# Pro_Trinket_Keyboard_V3_1.net
KiCad netlist of a schematic drawn in EAGLE
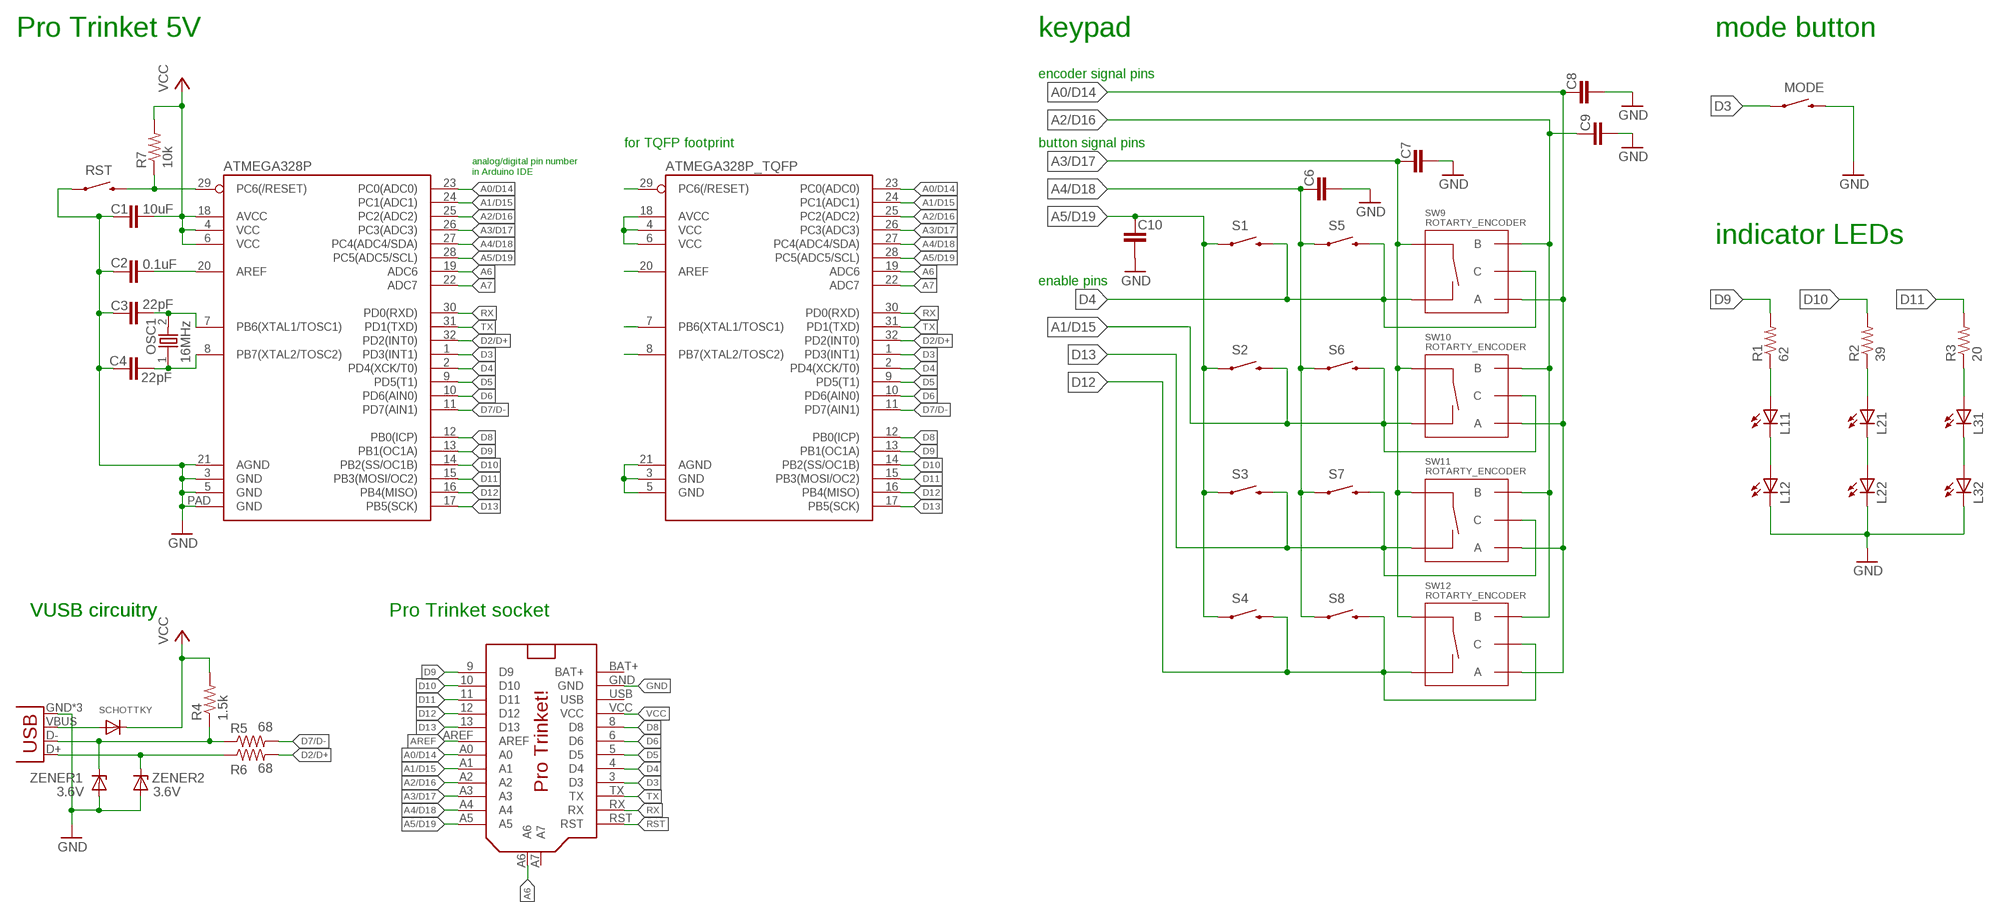
[diagram p0: schematic, sheet 1]

(export (version "E")
  (design (tool "Eeschema 10.0.6"))
  (components
    (comp (ref "ATMEGA328P")
      (value "ATMEGA328P_MLFMLF32")
      (footprint "eagle-import:MLF32-PAD")
      (libsource (lib "eagle-import") (part "ATMEGA328P_MLFMLF32"))
    )
    (comp (ref "ATMEGA328P_TQFP")
      (value "ATMEGA328P_TQFP")
      (footprint "eagle-import:TQFP32-08")
      (libsource (lib "eagle-import") (part "ATMEGA328P_TQFP"))
    )
    (comp (ref "C1")
      (value "10uF")
      (footprint "eagle-import:0603-CAP")
      (libsource (lib "eagle-import") (part "10UF-6.3V-20%(0603)"))
    )
    (comp (ref "C2")
      (value "0.1uF")
      (footprint "eagle-import:0603-CAP")
      (libsource (lib "eagle-import") (part "22PF-50V-5%(0603)"))
    )
    (comp (ref "C3")
      (value "22pF")
      (footprint "eagle-import:0603-CAP")
      (libsource (lib "eagle-import") (part "22PF-50V-5%(0603)"))
    )
    (comp (ref "C4")
      (value "22pF")
      (footprint "eagle-import:0603-CAP")
      (libsource (lib "eagle-import") (part "22PF-50V-5%(0603)"))
    )
    (comp (ref "C6")
      (value "22PF-50V-5%(0603)")
      (footprint "eagle-import:0603-CAP")
      (libsource (lib "eagle-import") (part "22PF-50V-5%(0603)"))
    )
    (comp (ref "C7")
      (value "22PF-50V-5%(0603)")
      (footprint "eagle-import:0603-CAP")
      (libsource (lib "eagle-import") (part "22PF-50V-5%(0603)"))
    )
    (comp (ref "C8")
      (value "22PF-50V-5%(0603)")
      (footprint "eagle-import:0603-CAP")
      (libsource (lib "eagle-import") (part "22PF-50V-5%(0603)"))
    )
    (comp (ref "C9")
      (value "22PF-50V-5%(0603)")
      (footprint "eagle-import:0603-CAP")
      (libsource (lib "eagle-import") (part "22PF-50V-5%(0603)"))
    )
    (comp (ref "C10")
      (value "22PF-50V-5%(0603)")
      (footprint "eagle-import:0603-CAP")
      (libsource (lib "eagle-import") (part "22PF-50V-5%(0603)"))
    )
    (comp (ref "JP1")
      (value "USB-MICROB")
      (footprint "eagle-import:USB-MICROB")
      (libsource (lib "eagle-import") (part "USB-MICROB"))
    )
    (comp (ref "L11")
      (value "LEDCHIPLED_0805")
      (footprint "eagle-import:CHIPLED_0805")
      (libsource (lib "eagle-import") (part "LEDCHIPLED_0805"))
    )
    (comp (ref "L12")
      (value "LEDCHIPLED_0805")
      (footprint "eagle-import:CHIPLED_0805")
      (libsource (lib "eagle-import") (part "LEDCHIPLED_0805"))
    )
    (comp (ref "L21")
      (value "LEDCHIPLED_0805")
      (footprint "eagle-import:CHIPLED_0805")
      (libsource (lib "eagle-import") (part "LEDCHIPLED_0805"))
    )
    (comp (ref "L22")
      (value "LEDCHIPLED_0805")
      (footprint "eagle-import:CHIPLED_0805")
      (libsource (lib "eagle-import") (part "LEDCHIPLED_0805"))
    )
    (comp (ref "L31")
      (value "LEDCHIPLED_0805")
      (footprint "eagle-import:CHIPLED_0805")
      (libsource (lib "eagle-import") (part "LEDCHIPLED_0805"))
    )
    (comp (ref "L32")
      (value "LEDCHIPLED_0805")
      (footprint "eagle-import:CHIPLED_0805")
      (libsource (lib "eagle-import") (part "LEDCHIPLED_0805"))
    )
    (comp (ref "MODE")
      (value "SWITCH-MOMENTARY-2SIDE_EZ")
      (footprint "eagle-import:TACTILE-PTH-SIDEEZ")
      (libsource (lib "eagle-import") (part "SWITCH-MOMENTARY-2SIDE_EZ"))
    )
    (comp (ref "OSC1")
      (value "16MHz")
      (footprint "eagle-import:HC-49U")
      (libsource (lib "eagle-import") (part "OSC-XTAL-HC-49U-SMD"))
    )
    (comp (ref "R1")
      (value "62")
      (footprint "eagle-import:M0805")
      (libsource (lib "eagle-import") (part "R-US_M0805"))
    )
    (comp (ref "R2")
      (value "39")
      (footprint "eagle-import:M0805")
      (libsource (lib "eagle-import") (part "R-US_M0805"))
    )
    (comp (ref "R3")
      (value "20")
      (footprint "eagle-import:M0805")
      (libsource (lib "eagle-import") (part "R-US_M0805"))
    )
    (comp (ref "R4")
      (value "1.5k")
      (footprint "eagle-import:0805")
      (libsource (lib "eagle-import") (part "RESISTOR0805-RES"))
    )
    (comp (ref "R5")
      (value "68")
      (footprint "eagle-import:0805")
      (libsource (lib "eagle-import") (part "RESISTOR0805-RES"))
    )
    (comp (ref "R6")
      (value "68")
      (footprint "eagle-import:0805")
      (libsource (lib "eagle-import") (part "RESISTOR0805-RES"))
    )
    (comp (ref "R7")
      (value "10k")
      (footprint "eagle-import:0805")
      (libsource (lib "eagle-import") (part "RESISTOR0805-RES"))
    )
    (comp (ref "RST")
      (value "SWITCH-MOMENTARY-2SIDE_EZ")
      (footprint "eagle-import:TACTILE-PTH-SIDEEZ")
      (libsource (lib "eagle-import") (part "SWITCH-MOMENTARY-2SIDE_EZ"))
    )
    (comp (ref "S1")
      (value "SWITCH-MOMENTARY-212MM")
      (footprint "eagle-import:TACTILE-PTH-12MM")
      (libsource (lib "eagle-import") (part "SWITCH-MOMENTARY-212MM"))
    )
    (comp (ref "S2")
      (value "SWITCH-MOMENTARY-212MM")
      (footprint "eagle-import:TACTILE-PTH-12MM")
      (libsource (lib "eagle-import") (part "SWITCH-MOMENTARY-212MM"))
    )
    (comp (ref "S3")
      (value "SWITCH-MOMENTARY-212MM")
      (footprint "eagle-import:TACTILE-PTH-12MM")
      (libsource (lib "eagle-import") (part "SWITCH-MOMENTARY-212MM"))
    )
    (comp (ref "S4")
      (value "SWITCH-MOMENTARY-212MM")
      (footprint "eagle-import:TACTILE-PTH-12MM")
      (libsource (lib "eagle-import") (part "SWITCH-MOMENTARY-212MM"))
    )
    (comp (ref "S5")
      (value "SWITCH-MOMENTARY-212MM")
      (footprint "eagle-import:TACTILE-PTH-12MM")
      (libsource (lib "eagle-import") (part "SWITCH-MOMENTARY-212MM"))
    )
    (comp (ref "S6")
      (value "SWITCH-MOMENTARY-212MM")
      (footprint "eagle-import:TACTILE-PTH-12MM")
      (libsource (lib "eagle-import") (part "SWITCH-MOMENTARY-212MM"))
    )
    (comp (ref "S7")
      (value "SWITCH-MOMENTARY-212MM")
      (footprint "eagle-import:TACTILE-PTH-12MM")
      (libsource (lib "eagle-import") (part "SWITCH-MOMENTARY-212MM"))
    )
    (comp (ref "S8")
      (value "SWITCH-MOMENTARY-212MM")
      (footprint "eagle-import:TACTILE-PTH-12MM")
      (libsource (lib "eagle-import") (part "SWITCH-MOMENTARY-212MM"))
    )
    (comp (ref "SCHOTTKY")
      (value "DIODESMA")
      (footprint "eagle-import:SMADIODE")
      (libsource (lib "eagle-import") (part "DIODESMA"))
    )
    (comp (ref "SW9")
      (value "ROTARTY_ENCODER")
      (footprint "eagle-import:ROTARY_ENC_PLAIN")
      (libsource (lib "eagle-import") (part "ROTARTY_ENCODER"))
    )
    (comp (ref "SW10")
      (value "ROTARTY_ENCODER")
      (footprint "eagle-import:ROTARY_ENC_PLAIN")
      (libsource (lib "eagle-import") (part "ROTARTY_ENCODER"))
    )
    (comp (ref "SW11")
      (value "ROTARTY_ENCODER")
      (footprint "eagle-import:ROTARY_ENC_PLAIN")
      (libsource (lib "eagle-import") (part "ROTARTY_ENCODER"))
    )
    (comp (ref "SW12")
      (value "ROTARTY_ENCODER")
      (footprint "eagle-import:ROTARY_ENC_PLAIN")
      (libsource (lib "eagle-import") (part "ROTARTY_ENCODER"))
    )
    (comp (ref "U$2")
      (value "PRO_TRINKET")
      (footprint "eagle-import:PROTRINKET")
      (libsource (lib "eagle-import") (part "PRO_TRINKET"))
    )
    (comp (ref "ZENER1")
      (value "3.6V")
      (footprint "eagle-import:SOD80C")
      (libsource (lib "eagle-import") (part "ZENER-DIODESOD80C"))
    )
    (comp (ref "ZENER2")
      (value "3.6V")
      (footprint "eagle-import:SOD80C")
      (libsource (lib "eagle-import") (part "ZENER-DIODESOD80C"))
    )
  )
  (nets
    (net (code "1") (name "/BAT+") (class "Default")
      (node (ref "U$2") (pin "BAT+") (pinfunction "BAT+_BAT+") (pintype "power_in"))
    )
    (net (code "2") (name "/USB") (class "Default")
      (node (ref "U$2") (pin "USB") (pinfunction "USB_USB") (pintype "power_in"))
    )
    (net (code "3") (name "/XTAL1") (class "Default")
      (node (ref "ATMEGA328P") (pin "7") (pinfunction "PB6(XTAL1/TOSC1)_7") (pintype "bidirectional"))
      (node (ref "ATMEGA328P_TQFP") (pin "7") (pinfunction "PB6(XTAL1/TOSC1)_7") (pintype "bidirectional"))
      (node (ref "C3") (pin "2") (pinfunction "2_2") (pintype "passive"))
      (node (ref "OSC1") (pin "2") (pinfunction "2_2") (pintype "passive"))
    )
    (net (code "4") (name "/XTAL2") (class "Default")
      (node (ref "ATMEGA328P") (pin "8") (pinfunction "PB7(XTAL2/TOSC2)_8") (pintype "bidirectional"))
      (node (ref "ATMEGA328P_TQFP") (pin "8") (pinfunction "PB7(XTAL2/TOSC2)_8") (pintype "bidirectional"))
      (node (ref "C4") (pin "1") (pinfunction "1_1") (pintype "passive"))
      (node (ref "OSC1") (pin "1") (pinfunction "1_1") (pintype "passive"))
    )
    (net (code "5") (name "A0{slash}D14") (class "Default")
      (node (ref "ATMEGA328P") (pin "23") (pinfunction "PC0(ADC0)_23") (pintype "bidirectional"))
      (node (ref "ATMEGA328P_TQFP") (pin "23") (pinfunction "PC0(ADC0)_23") (pintype "bidirectional"))
      (node (ref "C8") (pin "1") (pinfunction "1_1") (pintype "passive"))
      (node (ref "SW10") (pin "A") (pinfunction "A_A") (pintype "bidirectional"))
      (node (ref "SW11") (pin "A") (pinfunction "A_A") (pintype "bidirectional"))
      (node (ref "SW12") (pin "A") (pinfunction "A_A") (pintype "bidirectional"))
      (node (ref "SW9") (pin "A") (pinfunction "A_A") (pintype "bidirectional"))
      (node (ref "U$2") (pin "A0") (pinfunction "A0_A0") (pintype "bidirectional"))
    )
    (net (code "6") (name "A1{slash}D15") (class "Default")
      (node (ref "ATMEGA328P") (pin "24") (pinfunction "PC1(ADC1)_24") (pintype "bidirectional"))
      (node (ref "ATMEGA328P_TQFP") (pin "24") (pinfunction "PC1(ADC1)_24") (pintype "bidirectional"))
      (node (ref "S2") (pin "3") (pinfunction "2_3") (pintype "passive"))
      (node (ref "S2") (pin "4") (pinfunction "2_4") (pintype "passive"))
      (node (ref "S6") (pin "3") (pinfunction "2_3") (pintype "passive"))
      (node (ref "S6") (pin "4") (pinfunction "2_4") (pintype "passive"))
      (node (ref "SW10") (pin "C") (pinfunction "C_C") (pintype "bidirectional"))
      (node (ref "SW10") (pin "SW-") (pinfunction "SW-_SW-") (pintype "bidirectional"))
      (node (ref "U$2") (pin "A1") (pinfunction "A1_A1") (pintype "bidirectional"))
    )
    (net (code "7") (name "A2{slash}D16") (class "Default")
      (node (ref "ATMEGA328P") (pin "25") (pinfunction "PC2(ADC2)_25") (pintype "bidirectional"))
      (node (ref "ATMEGA328P_TQFP") (pin "25") (pinfunction "PC2(ADC2)_25") (pintype "bidirectional"))
      (node (ref "C9") (pin "1") (pinfunction "1_1") (pintype "passive"))
      (node (ref "SW10") (pin "B") (pinfunction "B_B") (pintype "bidirectional"))
      (node (ref "SW11") (pin "B") (pinfunction "B_B") (pintype "bidirectional"))
      (node (ref "SW12") (pin "B") (pinfunction "B_B") (pintype "bidirectional"))
      (node (ref "SW9") (pin "B") (pinfunction "B_B") (pintype "bidirectional"))
      (node (ref "U$2") (pin "A2") (pinfunction "A2_A2") (pintype "bidirectional"))
    )
    (net (code "8") (name "A3{slash}D17") (class "Default")
      (node (ref "ATMEGA328P") (pin "26") (pinfunction "PC3(ADC3)_26") (pintype "bidirectional"))
      (node (ref "ATMEGA328P_TQFP") (pin "26") (pinfunction "PC3(ADC3)_26") (pintype "bidirectional"))
      (node (ref "C7") (pin "1") (pinfunction "1_1") (pintype "passive"))
      (node (ref "SW10") (pin "SW+") (pinfunction "SW+_SW+") (pintype "bidirectional"))
      (node (ref "SW11") (pin "SW+") (pinfunction "SW+_SW+") (pintype "bidirectional"))
      (node (ref "SW12") (pin "SW+") (pinfunction "SW+_SW+") (pintype "bidirectional"))
      (node (ref "SW9") (pin "SW+") (pinfunction "SW+_SW+") (pintype "bidirectional"))
      (node (ref "U$2") (pin "A3") (pinfunction "A3_A3") (pintype "bidirectional"))
    )
    (net (code "9") (name "A4{slash}D18") (class "Default")
      (node (ref "ATMEGA328P") (pin "27") (pinfunction "PC4(ADC4/SDA)_27") (pintype "bidirectional"))
      (node (ref "ATMEGA328P_TQFP") (pin "27") (pinfunction "PC4(ADC4/SDA)_27") (pintype "bidirectional"))
      (node (ref "C6") (pin "1") (pinfunction "1_1") (pintype "passive"))
      (node (ref "S5") (pin "1") (pinfunction "1_1") (pintype "passive"))
      (node (ref "S5") (pin "2") (pinfunction "1_2") (pintype "passive"))
      (node (ref "S6") (pin "1") (pinfunction "1_1") (pintype "passive"))
      (node (ref "S6") (pin "2") (pinfunction "1_2") (pintype "passive"))
      (node (ref "S7") (pin "1") (pinfunction "1_1") (pintype "passive"))
      (node (ref "S7") (pin "2") (pinfunction "1_2") (pintype "passive"))
      (node (ref "S8") (pin "1") (pinfunction "1_1") (pintype "passive"))
      (node (ref "S8") (pin "2") (pinfunction "1_2") (pintype "passive"))
      (node (ref "U$2") (pin "A4") (pinfunction "A4_A4") (pintype "bidirectional"))
    )
    (net (code "10") (name "A5{slash}D19") (class "Default")
      (node (ref "ATMEGA328P") (pin "28") (pinfunction "PC5(ADC5/SCL)_28") (pintype "bidirectional"))
      (node (ref "ATMEGA328P_TQFP") (pin "28") (pinfunction "PC5(ADC5/SCL)_28") (pintype "bidirectional"))
      (node (ref "C10") (pin "1") (pinfunction "1_1") (pintype "passive"))
      (node (ref "S1") (pin "1") (pinfunction "1_1") (pintype "passive"))
      (node (ref "S1") (pin "2") (pinfunction "1_2") (pintype "passive"))
      (node (ref "S2") (pin "1") (pinfunction "1_1") (pintype "passive"))
      (node (ref "S2") (pin "2") (pinfunction "1_2") (pintype "passive"))
      (node (ref "S3") (pin "1") (pinfunction "1_1") (pintype "passive"))
      (node (ref "S3") (pin "2") (pinfunction "1_2") (pintype "passive"))
      (node (ref "S4") (pin "1") (pinfunction "1_1") (pintype "passive"))
      (node (ref "S4") (pin "2") (pinfunction "1_2") (pintype "passive"))
      (node (ref "U$2") (pin "A5") (pinfunction "A5_A5") (pintype "bidirectional"))
    )
    (net (code "11") (name "A6") (class "Default")
      (node (ref "ATMEGA328P") (pin "19") (pinfunction "ADC6_19") (pintype "bidirectional"))
      (node (ref "ATMEGA328P_TQFP") (pin "19") (pinfunction "ADC6_19") (pintype "bidirectional"))
      (node (ref "U$2") (pin "A6") (pinfunction "A6_A6") (pintype "passive"))
    )
    (net (code "12") (name "A7") (class "Default")
      (node (ref "ATMEGA328P") (pin "22") (pinfunction "ADC7_22") (pintype "bidirectional"))
      (node (ref "ATMEGA328P_TQFP") (pin "22") (pinfunction "ADC7_22") (pintype "bidirectional"))
    )
    (net (code "13") (name "AREF") (class "Default")
      (node (ref "ATMEGA328P") (pin "20") (pinfunction "AREF_20") (pintype "bidirectional"))
      (node (ref "ATMEGA328P_TQFP") (pin "20") (pinfunction "AREF_20") (pintype "bidirectional"))
      (node (ref "C2") (pin "2") (pinfunction "2_2") (pintype "passive"))
      (node (ref "U$2") (pin "AREF") (pinfunction "AREF_AREF") (pintype "passive"))
    )
    (net (code "14") (name "D2{slash}D+") (class "Default")
      (node (ref "ATMEGA328P") (pin "32") (pinfunction "PD2(INT0)_32") (pintype "bidirectional"))
      (node (ref "ATMEGA328P_TQFP") (pin "32") (pinfunction "PD2(INT0)_32") (pintype "bidirectional"))
      (node (ref "R6") (pin "2") (pinfunction "2_2") (pintype "passive"))
    )
    (net (code "15") (name "D3") (class "Default")
      (node (ref "ATMEGA328P") (pin "1") (pinfunction "PD3(INT1)_1") (pintype "bidirectional"))
      (node (ref "ATMEGA328P_TQFP") (pin "1") (pinfunction "PD3(INT1)_1") (pintype "bidirectional"))
      (node (ref "MODE") (pin "1") (pinfunction "1_1") (pintype "passive"))
      (node (ref "U$2") (pin "3") (pinfunction "D3_3") (pintype "bidirectional"))
    )
    (net (code "16") (name "D4") (class "Default")
      (node (ref "ATMEGA328P") (pin "2") (pinfunction "PD4(XCK/T0)_2") (pintype "bidirectional"))
      (node (ref "ATMEGA328P_TQFP") (pin "2") (pinfunction "PD4(XCK/T0)_2") (pintype "bidirectional"))
      (node (ref "S1") (pin "3") (pinfunction "2_3") (pintype "passive"))
      (node (ref "S1") (pin "4") (pinfunction "2_4") (pintype "passive"))
      (node (ref "S5") (pin "3") (pinfunction "2_3") (pintype "passive"))
      (node (ref "S5") (pin "4") (pinfunction "2_4") (pintype "passive"))
      (node (ref "SW9") (pin "C") (pinfunction "C_C") (pintype "bidirectional"))
      (node (ref "SW9") (pin "SW-") (pinfunction "SW-_SW-") (pintype "bidirectional"))
      (node (ref "U$2") (pin "4") (pinfunction "D4_4") (pintype "bidirectional"))
    )
    (net (code "17") (name "D5") (class "Default")
      (node (ref "ATMEGA328P") (pin "9") (pinfunction "PD5(T1)_9") (pintype "bidirectional"))
      (node (ref "ATMEGA328P_TQFP") (pin "9") (pinfunction "PD5(T1)_9") (pintype "bidirectional"))
      (node (ref "U$2") (pin "5") (pinfunction "D5_5") (pintype "bidirectional"))
    )
    (net (code "18") (name "D6") (class "Default")
      (node (ref "ATMEGA328P") (pin "10") (pinfunction "PD6(AIN0)_10") (pintype "bidirectional"))
      (node (ref "ATMEGA328P_TQFP") (pin "10") (pinfunction "PD6(AIN0)_10") (pintype "bidirectional"))
      (node (ref "U$2") (pin "6") (pinfunction "D6_6") (pintype "bidirectional"))
    )
    (net (code "19") (name "D7{slash}D-") (class "Default")
      (node (ref "ATMEGA328P") (pin "11") (pinfunction "PD7(AIN1)_11") (pintype "bidirectional"))
      (node (ref "ATMEGA328P_TQFP") (pin "11") (pinfunction "PD7(AIN1)_11") (pintype "bidirectional"))
      (node (ref "R5") (pin "2") (pinfunction "2_2") (pintype "passive"))
    )
    (net (code "20") (name "D8") (class "Default")
      (node (ref "ATMEGA328P") (pin "12") (pinfunction "PB0(ICP)_12") (pintype "bidirectional"))
      (node (ref "ATMEGA328P_TQFP") (pin "12") (pinfunction "PB0(ICP)_12") (pintype "bidirectional"))
      (node (ref "U$2") (pin "8") (pinfunction "D8_8") (pintype "bidirectional"))
    )
    (net (code "21") (name "D9") (class "Default")
      (node (ref "ATMEGA328P") (pin "13") (pinfunction "PB1(OC1A)_13") (pintype "bidirectional"))
      (node (ref "ATMEGA328P_TQFP") (pin "13") (pinfunction "PB1(OC1A)_13") (pintype "bidirectional"))
      (node (ref "R1") (pin "2") (pinfunction "2_2") (pintype "passive"))
      (node (ref "U$2") (pin "9") (pinfunction "D9_9") (pintype "bidirectional"))
    )
    (net (code "22") (name "D10") (class "Default")
      (node (ref "ATMEGA328P") (pin "14") (pinfunction "PB2(SS/OC1B)_14") (pintype "bidirectional"))
      (node (ref "ATMEGA328P_TQFP") (pin "14") (pinfunction "PB2(SS/OC1B)_14") (pintype "bidirectional"))
      (node (ref "R2") (pin "2") (pinfunction "2_2") (pintype "passive"))
      (node (ref "U$2") (pin "10") (pinfunction "D10_10") (pintype "bidirectional"))
    )
    (net (code "23") (name "D11") (class "Default")
      (node (ref "ATMEGA328P") (pin "15") (pinfunction "PB3(MOSI/OC2)_15") (pintype "bidirectional"))
      (node (ref "ATMEGA328P_TQFP") (pin "15") (pinfunction "PB3(MOSI/OC2)_15") (pintype "bidirectional"))
      (node (ref "R3") (pin "2") (pinfunction "2_2") (pintype "passive"))
      (node (ref "U$2") (pin "11") (pinfunction "D11_11") (pintype "bidirectional"))
    )
    (net (code "24") (name "D12") (class "Default")
      (node (ref "ATMEGA328P") (pin "16") (pinfunction "PB4(MISO)_16") (pintype "bidirectional"))
      (node (ref "ATMEGA328P_TQFP") (pin "16") (pinfunction "PB4(MISO)_16") (pintype "bidirectional"))
      (node (ref "S4") (pin "3") (pinfunction "2_3") (pintype "passive"))
      (node (ref "S4") (pin "4") (pinfunction "2_4") (pintype "passive"))
      (node (ref "S8") (pin "3") (pinfunction "2_3") (pintype "passive"))
      (node (ref "S8") (pin "4") (pinfunction "2_4") (pintype "passive"))
      (node (ref "SW12") (pin "C") (pinfunction "C_C") (pintype "bidirectional"))
      (node (ref "SW12") (pin "SW-") (pinfunction "SW-_SW-") (pintype "bidirectional"))
      (node (ref "U$2") (pin "12") (pinfunction "D12_12") (pintype "bidirectional"))
    )
    (net (code "25") (name "D13") (class "Default")
      (node (ref "ATMEGA328P") (pin "17") (pinfunction "PB5(SCK)_17") (pintype "bidirectional"))
      (node (ref "ATMEGA328P_TQFP") (pin "17") (pinfunction "PB5(SCK)_17") (pintype "bidirectional"))
      (node (ref "S3") (pin "3") (pinfunction "2_3") (pintype "passive"))
      (node (ref "S3") (pin "4") (pinfunction "2_4") (pintype "passive"))
      (node (ref "S7") (pin "3") (pinfunction "2_3") (pintype "passive"))
      (node (ref "S7") (pin "4") (pinfunction "2_4") (pintype "passive"))
      (node (ref "SW11") (pin "C") (pinfunction "C_C") (pintype "bidirectional"))
      (node (ref "SW11") (pin "SW-") (pinfunction "SW-_SW-") (pintype "bidirectional"))
      (node (ref "U$2") (pin "13") (pinfunction "D13_13") (pintype "bidirectional"))
    )
    (net (code "26") (name "GND") (class "Default")
      (node (ref "ATMEGA328P") (pin "21") (pinfunction "AGND_21") (pintype "bidirectional"))
      (node (ref "ATMEGA328P") (pin "3") (pinfunction "GND_3") (pintype "bidirectional"))
      (node (ref "ATMEGA328P") (pin "5") (pinfunction "GND_5") (pintype "bidirectional"))
      (node (ref "ATMEGA328P") (pin "PAD") (pinfunction "GND_PAD") (pintype "bidirectional"))
      (node (ref "ATMEGA328P_TQFP") (pin "21") (pinfunction "AGND_21") (pintype "bidirectional"))
      (node (ref "ATMEGA328P_TQFP") (pin "3") (pinfunction "GND_3") (pintype "bidirectional"))
      (node (ref "ATMEGA328P_TQFP") (pin "5") (pinfunction "GND_5") (pintype "bidirectional"))
      (node (ref "C1") (pin "1") (pinfunction "1_1") (pintype "passive"))
      (node (ref "C10") (pin "2") (pinfunction "2_2") (pintype "passive"))
      (node (ref "C2") (pin "1") (pinfunction "1_1") (pintype "passive"))
      (node (ref "C3") (pin "1") (pinfunction "1_1") (pintype "passive"))
      (node (ref "C4") (pin "2") (pinfunction "2_2") (pintype "passive"))
      (node (ref "C6") (pin "2") (pinfunction "2_2") (pintype "passive"))
      (node (ref "C7") (pin "2") (pinfunction "2_2") (pintype "passive"))
      (node (ref "C8") (pin "2") (pinfunction "2_2") (pintype "passive"))
      (node (ref "C9") (pin "2") (pinfunction "2_2") (pintype "passive"))
      (node (ref "JP1") (pin "GND") (pinfunction "GND_GND") (pintype "bidirectional"))
      (node (ref "JP1") (pin "MT1") (pinfunction "GND_MT1") (pintype "bidirectional"))
      (node (ref "JP1") (pin "MT2") (pinfunction "GND_MT2") (pintype "bidirectional"))
      (node (ref "L12") (pin "C") (pinfunction "C_C") (pintype "passive"))
      (node (ref "L22") (pin "C") (pinfunction "C_C") (pintype "passive"))
      (node (ref "L32") (pin "C") (pinfunction "C_C") (pintype "passive"))
      (node (ref "MODE") (pin "2") (pinfunction "2_2") (pintype "passive"))
      (node (ref "RST") (pin "1") (pinfunction "1_1") (pintype "passive"))
      (node (ref "U$2") (pin "GND") (pinfunction "GND_GND") (pintype "power_in"))
      (node (ref "ZENER1") (pin "A") (pinfunction "A_A") (pintype "passive"))
      (node (ref "ZENER2") (pin "A") (pinfunction "A_A") (pintype "passive"))
    )
    (net (code "27") (name "Net-(JP1-PadD+)") (class "Default")
      (node (ref "JP1") (pin "D+") (pinfunction "D+_D+") (pintype "bidirectional"))
      (node (ref "R6") (pin "1") (pinfunction "1_1") (pintype "passive"))
      (node (ref "ZENER2") (pin "C") (pinfunction "C_C") (pintype "passive"))
    )
    (net (code "28") (name "Net-(JP1-PadD-)") (class "Default")
      (node (ref "JP1") (pin "D-") (pinfunction "D-_D-") (pintype "bidirectional"))
      (node (ref "R4") (pin "1") (pinfunction "1_1") (pintype "passive"))
      (node (ref "R5") (pin "1") (pinfunction "1_1") (pintype "passive"))
      (node (ref "ZENER1") (pin "C") (pinfunction "C_C") (pintype "passive"))
    )
    (net (code "29") (name "Net-(JP1-PadVBUS)") (class "Default")
      (node (ref "JP1") (pin "VBUS") (pinfunction "VBUS_VBUS") (pintype "bidirectional"))
      (node (ref "SCHOTTKY") (pin "A") (pinfunction "A_A") (pintype "passive"))
    )
    (net (code "30") (name "Net-(L11-PadA)") (class "Default")
      (node (ref "L11") (pin "A") (pinfunction "A_A") (pintype "passive"))
      (node (ref "R1") (pin "1") (pinfunction "1_1") (pintype "passive"))
    )
    (net (code "31") (name "Net-(L11-PadC)") (class "Default")
      (node (ref "L11") (pin "C") (pinfunction "C_C") (pintype "passive"))
      (node (ref "L12") (pin "A") (pinfunction "A_A") (pintype "passive"))
    )
    (net (code "32") (name "Net-(L21-PadA)") (class "Default")
      (node (ref "L21") (pin "A") (pinfunction "A_A") (pintype "passive"))
      (node (ref "R2") (pin "1") (pinfunction "1_1") (pintype "passive"))
    )
    (net (code "33") (name "Net-(L21-PadC)") (class "Default")
      (node (ref "L21") (pin "C") (pinfunction "C_C") (pintype "passive"))
      (node (ref "L22") (pin "A") (pinfunction "A_A") (pintype "passive"))
    )
    (net (code "34") (name "Net-(L31-PadA)") (class "Default")
      (node (ref "L31") (pin "A") (pinfunction "A_A") (pintype "passive"))
      (node (ref "R3") (pin "1") (pinfunction "1_1") (pintype "passive"))
    )
    (net (code "35") (name "Net-(L31-PadC)") (class "Default")
      (node (ref "L31") (pin "C") (pinfunction "C_C") (pintype "passive"))
      (node (ref "L32") (pin "A") (pinfunction "A_A") (pintype "passive"))
    )
    (net (code "36") (name "RST") (class "Default")
      (node (ref "ATMEGA328P") (pin "29") (pinfunction "PC6(/RESET)_29") (pintype "bidirectional"))
      (node (ref "ATMEGA328P_TQFP") (pin "29") (pinfunction "PC6(/RESET)_29") (pintype "bidirectional"))
      (node (ref "R7") (pin "1") (pinfunction "1_1") (pintype "passive"))
      (node (ref "RST") (pin "2") (pinfunction "2_2") (pintype "passive"))
      (node (ref "U$2") (pin "RST") (pinfunction "RST_RST") (pintype "passive"))
    )
    (net (code "37") (name "RX") (class "Default")
      (node (ref "ATMEGA328P") (pin "30") (pinfunction "PD0(RXD)_30") (pintype "bidirectional"))
      (node (ref "ATMEGA328P_TQFP") (pin "30") (pinfunction "PD0(RXD)_30") (pintype "bidirectional"))
      (node (ref "U$2") (pin "RX") (pinfunction "RX_RX") (pintype "bidirectional"))
    )
    (net (code "38") (name "TX") (class "Default")
      (node (ref "ATMEGA328P") (pin "31") (pinfunction "PD1(TXD)_31") (pintype "bidirectional"))
      (node (ref "ATMEGA328P_TQFP") (pin "31") (pinfunction "PD1(TXD)_31") (pintype "bidirectional"))
      (node (ref "U$2") (pin "TX") (pinfunction "TX_TX") (pintype "bidirectional"))
    )
    (net (code "39") (name "VCC") (class "Default")
      (node (ref "ATMEGA328P") (pin "18") (pinfunction "AVCC_18") (pintype "bidirectional"))
      (node (ref "ATMEGA328P") (pin "4") (pinfunction "VCC_4") (pintype "bidirectional"))
      (node (ref "ATMEGA328P") (pin "6") (pinfunction "VCC_6") (pintype "bidirectional"))
      (node (ref "ATMEGA328P_TQFP") (pin "18") (pinfunction "AVCC_18") (pintype "bidirectional"))
      (node (ref "ATMEGA328P_TQFP") (pin "4") (pinfunction "VCC_4") (pintype "bidirectional"))
      (node (ref "ATMEGA328P_TQFP") (pin "6") (pinfunction "VCC_6") (pintype "bidirectional"))
      (node (ref "C1") (pin "2") (pinfunction "2_2") (pintype "passive"))
      (node (ref "R4") (pin "2") (pinfunction "2_2") (pintype "passive"))
      (node (ref "R7") (pin "2") (pinfunction "2_2") (pintype "passive"))
      (node (ref "SCHOTTKY") (pin "C") (pinfunction "C_C") (pintype "passive"))
      (node (ref "U$2") (pin "VCC") (pinfunction "VCC_VCC") (pintype "power_in"))
    )
    (net (code "40") (name "unconnected-(U$2-PadA7)") (class "Default")
      (node (ref "U$2") (pin "A7") (pinfunction "A7_A7") (pintype "passive"))
    )
  )
)
